# HIVE_BOARD_MISC.net
KiCad netlist of a schematic drawn in Altium Designer
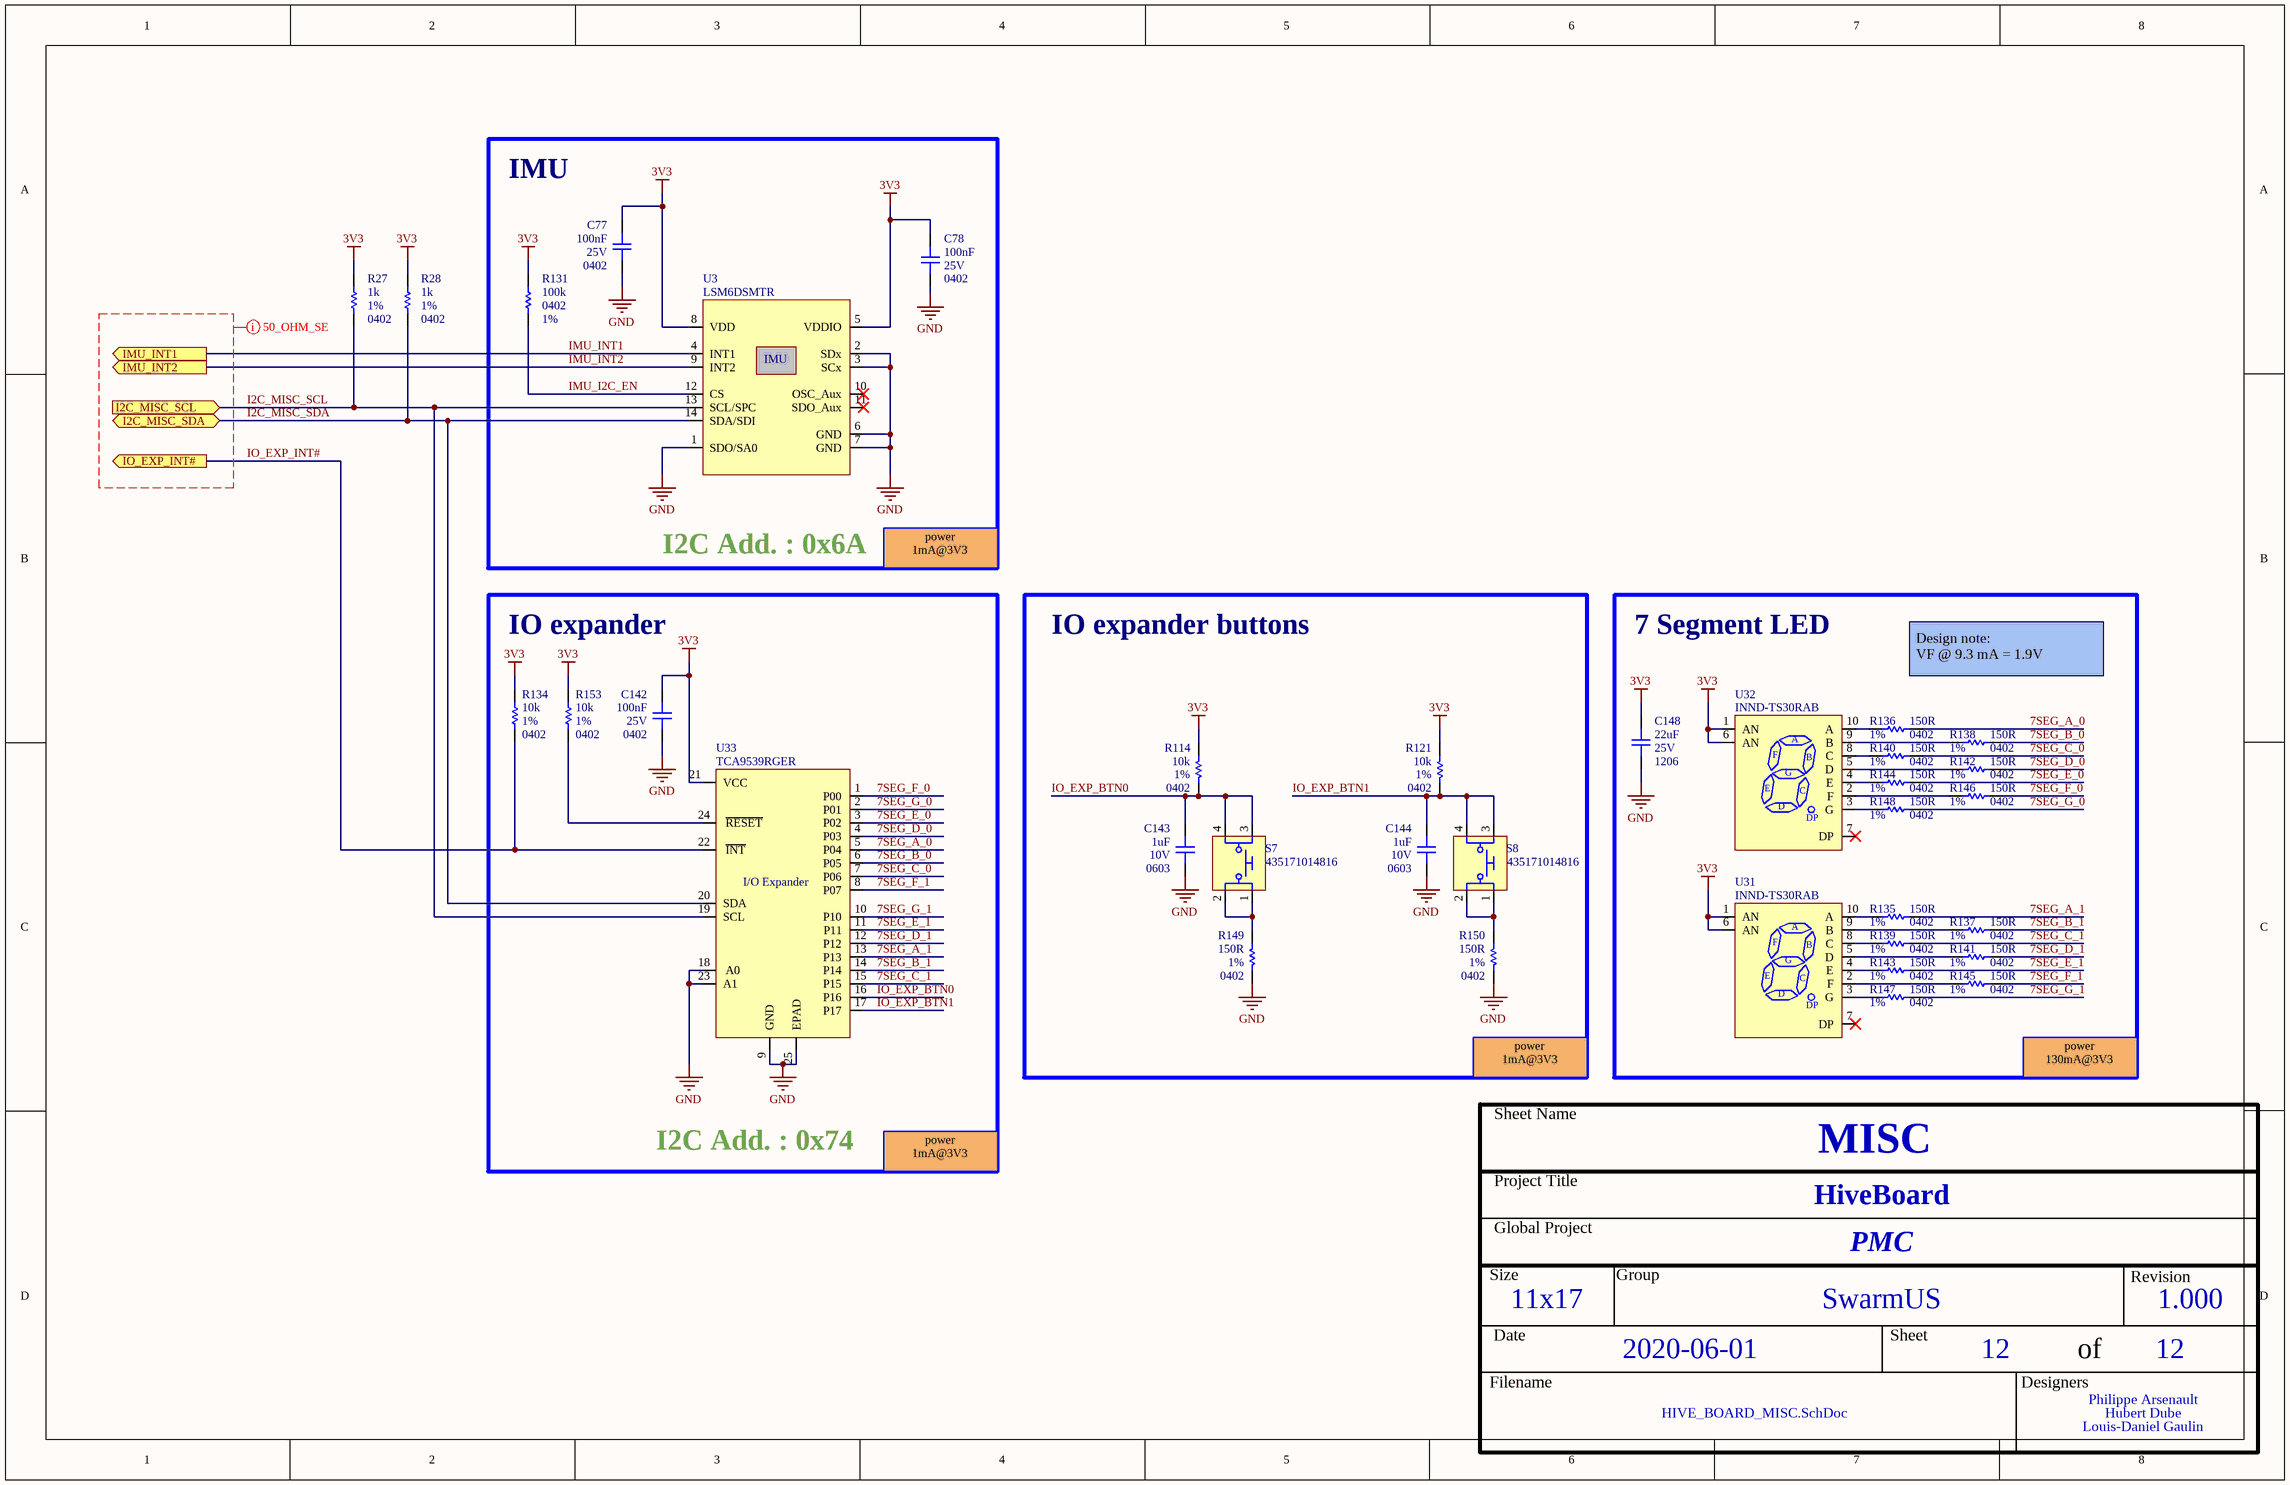
[diagram p0: HIVE_BOARD_MISC.SchDoc]

(export (version "E")
  (design (tool "Eeschema 10.0.6"))
  (components
    (comp (ref "C77")
      (value "100nF")
      (footprint "CAP_CER_0402")
      (description "CAP - CER 0.1µF 10% 25V X7R - 0402")
      (fields
        (field (name "TOLERANCE") "10%")
        (field (name "PACKAGE") "0402")
        (field (name "VOLTAGE RATING") "25V")
        (field (name "Comment") "CGA2B3X7R1E104K050BB")
        (field (name "CREATEDBY/DATE") "Nicolas Roy 2018-11-07")
        (field (name "VERIFIEDBY") "Nicolas V. (2019-01-22)")
      )
      (libsource (lib "GRAMS_MASTER_LIB") (part "CAP_CER_CGA2B3X7R1E104K050BB"))
    )
    (comp (ref "C78")
      (value "100nF")
      (footprint "CAP_CER_0402")
      (description "CAP - CER 0.1µF 10% 25V X7R - 0402")
      (fields
        (field (name "TOLERANCE") "10%")
        (field (name "PACKAGE") "0402")
        (field (name "VOLTAGE RATING") "25V")
        (field (name "Comment") "CGA2B3X7R1E104K050BB")
        (field (name "CREATEDBY/DATE") "Nicolas Roy 2018-11-07")
        (field (name "VERIFIEDBY") "Nicolas V. (2019-01-22)")
      )
      (libsource (lib "GRAMS_MASTER_LIB") (part "CAP_CER_CGA2B3X7R1E104K050BB"))
    )
    (comp (ref "C142")
      (value "100nF")
      (footprint "CAP_CER_0402")
      (description "CAP - CER 0.1µF 10% 25V X7R - 0402")
      (fields
        (field (name "TOLERANCE") "10%")
        (field (name "PACKAGE") "0402")
        (field (name "VOLTAGE RATING") "25V")
        (field (name "Comment") "CGA2B3X7R1E104K050BB")
        (field (name "CREATEDBY/DATE") "Nicolas Roy 2018-11-07")
        (field (name "VERIFIEDBY") "Nicolas V. (2019-01-22)")
      )
      (libsource (lib "GRAMS_MASTER_LIB") (part "CAP_CER_CGA2B3X7R1E104K050BB"))
    )
    (comp (ref "C143")
      (value "1uF")
      (footprint "CAP_CER_0603")
      (description "CAP - CER 1uF 10V 10% X5R - 0603")
      (fields
        (field (name "TOLERANCE") "10%")
        (field (name "PACKAGE") "0603")
        (field (name "VOLTAGE RATING") "10V")
        (field (name "Comment") "C0603C105K8PACTU")
        (field (name "CREATEDBY/DATE") "Hubert Dube - 21/07/20")
        (field (name "VERIFIEDBY") "Louis-Daniel Gaulin - 21/07/20")
      )
      (libsource (lib "SWARMUS_LIB") (part "CAP_CER_C0603C105K8PACTU"))
    )
    (comp (ref "C144")
      (value "1uF")
      (footprint "CAP_CER_0603")
      (description "CAP - CER 1uF 10V 10% X5R - 0603")
      (fields
        (field (name "TOLERANCE") "10%")
        (field (name "PACKAGE") "0603")
        (field (name "VOLTAGE RATING") "10V")
        (field (name "Comment") "C0603C105K8PACTU")
        (field (name "CREATEDBY/DATE") "Hubert Dube - 21/07/20")
        (field (name "VERIFIEDBY") "Louis-Daniel Gaulin - 21/07/20")
      )
      (libsource (lib "SWARMUS_LIB") (part "CAP_CER_C0603C105K8PACTU"))
    )
    (comp (ref "C148")
      (value "22uF")
      (footprint "CAP_CER_1206")
      (description "CAP - CER 22uF 10% 25V X5R - 1206")
      (fields
        (field (name "TOLERANCE") "10%")
        (field (name "PACKAGE") "1206")
        (field (name "VOLTAGE RATING") "25V")
        (field (name "Comment") "CL31A226KAHNNNE")
        (field (name "CREATEDBY/DATE") "Philippe Arsenault/21 Janvier 2020")
        (field (name "VERIFIEDBY") "C.Paulin - 28/01/2020")
      )
      (libsource (lib "GRAMS_MASTER_LIB") (part "CAP_CER_CL31A226KAHNNNE"))
    )
    (comp (ref "R27")
      (value "1k")
      (footprint "RES_0402")
      (description "RES - 1K OHM 1% 1/16W - 0402")
      (fields
        (field (name "TOLERANCE") "1%")
        (field (name "PACKAGE") "0402")
        (field (name "Comment") "RC0402FR-071KL")
        (field (name "CREATEDBY/DATE") "Jonathan Bouchard 2018-07-05")
        (field (name "VERIFIEDBY") "Arnaud Samson 16-07-18")
      )
      (libsource (lib "GRAMS_MASTER_LIB") (part "RES_RC0402FR-071KL"))
    )
    (comp (ref "R28")
      (value "1k")
      (footprint "RES_0402")
      (description "RES - 1K OHM 1% 1/16W - 0402")
      (fields
        (field (name "TOLERANCE") "1%")
        (field (name "PACKAGE") "0402")
        (field (name "Comment") "RC0402FR-071KL")
        (field (name "CREATEDBY/DATE") "Jonathan Bouchard 2018-07-05")
        (field (name "VERIFIEDBY") "Arnaud Samson 16-07-18")
      )
      (libsource (lib "GRAMS_MASTER_LIB") (part "RES_RC0402FR-071KL"))
    )
    (comp (ref "R114")
      (value "10k")
      (footprint "RES_0402")
      (description "RES - 10K OHMS 1% 1/16W - 0402")
      (fields
        (field (name "TOLERANCE") "1%")
        (field (name "PACKAGE") "0402")
        (field (name "Comment") "RC0402FR-0710KL")
        (field (name "CREATEDBY/DATE") "Nicolas V. (2018-11-20)")
        (field (name "VERIFIEDBY") "Nicolas V. (2018-11-20)")
      )
      (libsource (lib "GRAMS_MASTER_LIB") (part "RES_RC0402FR-0710KL"))
    )
    (comp (ref "R121")
      (value "10k")
      (footprint "RES_0402")
      (description "RES - 10K OHMS 1% 1/16W - 0402")
      (fields
        (field (name "TOLERANCE") "1%")
        (field (name "PACKAGE") "0402")
        (field (name "Comment") "RC0402FR-0710KL")
        (field (name "CREATEDBY/DATE") "Nicolas V. (2018-11-20)")
        (field (name "VERIFIEDBY") "Nicolas V. (2018-11-20)")
      )
      (libsource (lib "GRAMS_MASTER_LIB") (part "RES_RC0402FR-0710KL"))
    )
    (comp (ref "R131")
      (value "100k")
      (footprint "RES_0402")
      (description "RES - 100K 1% 1/16W - 0402")
      (fields
        (field (name "TOLERANCE") "1%")
        (field (name "PACKAGE") "0402")
        (field (name "Comment") "RC0402FR-07100KL")
        (field (name "CREATEDBY/DATE") "Keven Deslandes 2018-10-19")
        (field (name "VERIFIEDBY") "Caroline Paulin - 18/12/2018")
      )
      (libsource (lib "GRAMS_MASTER_LIB") (part "RES_RC0402FR-07100KL"))
    )
    (comp (ref "R134")
      (value "10k")
      (footprint "RES_0402")
      (description "RES - 10K OHMS 1% 1/16W - 0402")
      (fields
        (field (name "TOLERANCE") "1%")
        (field (name "PACKAGE") "0402")
        (field (name "Comment") "RC0402FR-0710KL")
        (field (name "CREATEDBY/DATE") "Nicolas V. (2018-11-20)")
        (field (name "VERIFIEDBY") "Nicolas V. (2018-11-20)")
      )
      (libsource (lib "GRAMS_MASTER_LIB") (part "RES_RC0402FR-0710KL"))
    )
    (comp (ref "R135")
      (value "150R")
      (footprint "RES_0402")
      (description "RES - 150R 1% 1/16W - 0402")
      (fields
        (field (name "TOLERANCE") "1%")
        (field (name "PACKAGE") "0402")
        (field (name "Comment") "RC0402FR-07150RL")
        (field (name "CREATEDBY/DATE") "Jonathan Bouchard 2019-03-25")
        (field (name "VERIFIEDBY") "Nicolas V. (2019-05-02)")
      )
      (libsource (lib "GRAMS_MASTER_LIB") (part "RES_RC0402FR-07150RL"))
    )
    (comp (ref "R136")
      (value "150R")
      (footprint "RES_0402")
      (description "RES - 150R 1% 1/16W - 0402")
      (fields
        (field (name "TOLERANCE") "1%")
        (field (name "PACKAGE") "0402")
        (field (name "Comment") "RC0402FR-07150RL")
        (field (name "CREATEDBY/DATE") "Jonathan Bouchard 2019-03-25")
        (field (name "VERIFIEDBY") "Nicolas V. (2019-05-02)")
      )
      (libsource (lib "GRAMS_MASTER_LIB") (part "RES_RC0402FR-07150RL"))
    )
    (comp (ref "R137")
      (value "150R")
      (footprint "RES_0402")
      (description "RES - 150R 1% 1/16W - 0402")
      (fields
        (field (name "TOLERANCE") "1%")
        (field (name "PACKAGE") "0402")
        (field (name "Comment") "RC0402FR-07150RL")
        (field (name "CREATEDBY/DATE") "Jonathan Bouchard 2019-03-25")
        (field (name "VERIFIEDBY") "Nicolas V. (2019-05-02)")
      )
      (libsource (lib "GRAMS_MASTER_LIB") (part "RES_RC0402FR-07150RL"))
    )
    (comp (ref "R138")
      (value "150R")
      (footprint "RES_0402")
      (description "RES - 150R 1% 1/16W - 0402")
      (fields
        (field (name "TOLERANCE") "1%")
        (field (name "PACKAGE") "0402")
        (field (name "Comment") "RC0402FR-07150RL")
        (field (name "CREATEDBY/DATE") "Jonathan Bouchard 2019-03-25")
        (field (name "VERIFIEDBY") "Nicolas V. (2019-05-02)")
      )
      (libsource (lib "GRAMS_MASTER_LIB") (part "RES_RC0402FR-07150RL"))
    )
    (comp (ref "R139")
      (value "150R")
      (footprint "RES_0402")
      (description "RES - 150R 1% 1/16W - 0402")
      (fields
        (field (name "TOLERANCE") "1%")
        (field (name "PACKAGE") "0402")
        (field (name "Comment") "RC0402FR-07150RL")
        (field (name "CREATEDBY/DATE") "Jonathan Bouchard 2019-03-25")
        (field (name "VERIFIEDBY") "Nicolas V. (2019-05-02)")
      )
      (libsource (lib "GRAMS_MASTER_LIB") (part "RES_RC0402FR-07150RL"))
    )
    (comp (ref "R140")
      (value "150R")
      (footprint "RES_0402")
      (description "RES - 150R 1% 1/16W - 0402")
      (fields
        (field (name "TOLERANCE") "1%")
        (field (name "PACKAGE") "0402")
        (field (name "Comment") "RC0402FR-07150RL")
        (field (name "CREATEDBY/DATE") "Jonathan Bouchard 2019-03-25")
        (field (name "VERIFIEDBY") "Nicolas V. (2019-05-02)")
      )
      (libsource (lib "GRAMS_MASTER_LIB") (part "RES_RC0402FR-07150RL"))
    )
    (comp (ref "R141")
      (value "150R")
      (footprint "RES_0402")
      (description "RES - 150R 1% 1/16W - 0402")
      (fields
        (field (name "TOLERANCE") "1%")
        (field (name "PACKAGE") "0402")
        (field (name "Comment") "RC0402FR-07150RL")
        (field (name "CREATEDBY/DATE") "Jonathan Bouchard 2019-03-25")
        (field (name "VERIFIEDBY") "Nicolas V. (2019-05-02)")
      )
      (libsource (lib "GRAMS_MASTER_LIB") (part "RES_RC0402FR-07150RL"))
    )
    (comp (ref "R142")
      (value "150R")
      (footprint "RES_0402")
      (description "RES - 150R 1% 1/16W - 0402")
      (fields
        (field (name "TOLERANCE") "1%")
        (field (name "PACKAGE") "0402")
        (field (name "Comment") "RC0402FR-07150RL")
        (field (name "CREATEDBY/DATE") "Jonathan Bouchard 2019-03-25")
        (field (name "VERIFIEDBY") "Nicolas V. (2019-05-02)")
      )
      (libsource (lib "GRAMS_MASTER_LIB") (part "RES_RC0402FR-07150RL"))
    )
    (comp (ref "R143")
      (value "150R")
      (footprint "RES_0402")
      (description "RES - 150R 1% 1/16W - 0402")
      (fields
        (field (name "TOLERANCE") "1%")
        (field (name "PACKAGE") "0402")
        (field (name "Comment") "RC0402FR-07150RL")
        (field (name "CREATEDBY/DATE") "Jonathan Bouchard 2019-03-25")
        (field (name "VERIFIEDBY") "Nicolas V. (2019-05-02)")
      )
      (libsource (lib "GRAMS_MASTER_LIB") (part "RES_RC0402FR-07150RL"))
    )
    (comp (ref "R144")
      (value "150R")
      (footprint "RES_0402")
      (description "RES - 150R 1% 1/16W - 0402")
      (fields
        (field (name "TOLERANCE") "1%")
        (field (name "PACKAGE") "0402")
        (field (name "Comment") "RC0402FR-07150RL")
        (field (name "CREATEDBY/DATE") "Jonathan Bouchard 2019-03-25")
        (field (name "VERIFIEDBY") "Nicolas V. (2019-05-02)")
      )
      (libsource (lib "GRAMS_MASTER_LIB") (part "RES_RC0402FR-07150RL"))
    )
    (comp (ref "R145")
      (value "150R")
      (footprint "RES_0402")
      (description "RES - 150R 1% 1/16W - 0402")
      (fields
        (field (name "TOLERANCE") "1%")
        (field (name "PACKAGE") "0402")
        (field (name "Comment") "RC0402FR-07150RL")
        (field (name "CREATEDBY/DATE") "Jonathan Bouchard 2019-03-25")
        (field (name "VERIFIEDBY") "Nicolas V. (2019-05-02)")
      )
      (libsource (lib "GRAMS_MASTER_LIB") (part "RES_RC0402FR-07150RL"))
    )
    (comp (ref "R146")
      (value "150R")
      (footprint "RES_0402")
      (description "RES - 150R 1% 1/16W - 0402")
      (fields
        (field (name "TOLERANCE") "1%")
        (field (name "PACKAGE") "0402")
        (field (name "Comment") "RC0402FR-07150RL")
        (field (name "CREATEDBY/DATE") "Jonathan Bouchard 2019-03-25")
        (field (name "VERIFIEDBY") "Nicolas V. (2019-05-02)")
      )
      (libsource (lib "GRAMS_MASTER_LIB") (part "RES_RC0402FR-07150RL"))
    )
    (comp (ref "R147")
      (value "150R")
      (footprint "RES_0402")
      (description "RES - 150R 1% 1/16W - 0402")
      (fields
        (field (name "TOLERANCE") "1%")
        (field (name "PACKAGE") "0402")
        (field (name "Comment") "RC0402FR-07150RL")
        (field (name "CREATEDBY/DATE") "Jonathan Bouchard 2019-03-25")
        (field (name "VERIFIEDBY") "Nicolas V. (2019-05-02)")
      )
      (libsource (lib "GRAMS_MASTER_LIB") (part "RES_RC0402FR-07150RL"))
    )
    (comp (ref "R148")
      (value "150R")
      (footprint "RES_0402")
      (description "RES - 150R 1% 1/16W - 0402")
      (fields
        (field (name "TOLERANCE") "1%")
        (field (name "PACKAGE") "0402")
        (field (name "Comment") "RC0402FR-07150RL")
        (field (name "CREATEDBY/DATE") "Jonathan Bouchard 2019-03-25")
        (field (name "VERIFIEDBY") "Nicolas V. (2019-05-02)")
      )
      (libsource (lib "GRAMS_MASTER_LIB") (part "RES_RC0402FR-07150RL"))
    )
    (comp (ref "R149")
      (value "150R")
      (footprint "RES_0402")
      (description "RES - 150R 1% 1/16W - 0402")
      (fields
        (field (name "TOLERANCE") "1%")
        (field (name "PACKAGE") "0402")
        (field (name "Comment") "RC0402FR-07150RL")
        (field (name "CREATEDBY/DATE") "Jonathan Bouchard 2019-03-25")
        (field (name "VERIFIEDBY") "Nicolas V. (2019-05-02)")
      )
      (libsource (lib "GRAMS_MASTER_LIB") (part "RES_RC0402FR-07150RL"))
    )
    (comp (ref "R150")
      (value "150R")
      (footprint "RES_0402")
      (description "RES - 150R 1% 1/16W - 0402")
      (fields
        (field (name "TOLERANCE") "1%")
        (field (name "PACKAGE") "0402")
        (field (name "Comment") "RC0402FR-07150RL")
        (field (name "CREATEDBY/DATE") "Jonathan Bouchard 2019-03-25")
        (field (name "VERIFIEDBY") "Nicolas V. (2019-05-02)")
      )
      (libsource (lib "GRAMS_MASTER_LIB") (part "RES_RC0402FR-07150RL"))
    )
    (comp (ref "R153")
      (value "10k")
      (footprint "RES_0402")
      (description "RES - 10K OHMS 1% 1/16W - 0402")
      (fields
        (field (name "TOLERANCE") "1%")
        (field (name "PACKAGE") "0402")
        (field (name "Comment") "RC0402FR-0710KL")
        (field (name "CREATEDBY/DATE") "Nicolas V. (2018-11-20)")
        (field (name "VERIFIEDBY") "Nicolas V. (2018-11-20)")
      )
      (libsource (lib "GRAMS_MASTER_LIB") (part "RES_RC0402FR-0710KL"))
    )
    (comp (ref "S7")
      (value "435171014816")
      (footprint "SWI_TACT_435171014816")
      (description "SWI - SWITCH TACTILE SPST-NO 0.05A 12V -SMD")
      (fields
        (field (name "CREATEDBY/DATE") "Hubert Dube - 22/07/20")
        (field (name "VERIFIEDBY") "Louis-Daniel Gaulin / 12-11-2020")
      )
      (libsource (lib "SWARMUS_LIB") (part "SWI_TACT_435171014816"))
    )
    (comp (ref "S8")
      (value "435171014816")
      (footprint "SWI_TACT_435171014816")
      (description "SWI - SWITCH TACTILE SPST-NO 0.05A 12V -SMD")
      (fields
        (field (name "CREATEDBY/DATE") "Hubert Dube - 22/07/20")
        (field (name "VERIFIEDBY") "Louis-Daniel Gaulin / 12-11-2020")
      )
      (libsource (lib "SWARMUS_LIB") (part "SWI_TACT_435171014816"))
    )
    (comp (ref "U3")
      (value "LSM6DSMTR")
      (footprint "SEN_IMU_LSM6DSMTR")
      (description "SEN_IMU -  ACCEL/GYRO 6 Axis I2C/SPI - 14-VFLGA")
      (fields
        (field (name "CREATEDBY/DATE") "Louis-Daniel Gaulin / 06-10-2020")
        (field (name "VERIFIEDBY") "Philippe Arsenault/2020-11-06")
      )
      (libsource (lib "SWARMUS_LIB") (part "SEN_IMU_LSM6DSMTR"))
    )
    (comp (ref "U31")
      (value "INND-TS30RAB")
      (footprint "LED_7SEG_INND-TS30RAB")
      (description "LED_7SEG  - LED Character and Numeric Red 7-Segment 1 Character Common Anode 2V - 10-TH")
      (fields
        (field (name "CREATEDBY/DATE") "Louis-Daniel Gaulin / 10-05-2021")
        (field (name "VERIFIEDBY") "Philippe Arsenault/10-05-2021")
      )
      (libsource (lib "SWARMUS_LIB") (part "LED_7SEG_INND-TS30RAB"))
    )
    (comp (ref "U32")
      (value "INND-TS30RAB")
      (footprint "LED_7SEG_INND-TS30RAB")
      (description "LED_7SEG  - LED Character and Numeric Red 7-Segment 1 Character Common Anode 2V - 10-TH")
      (fields
        (field (name "CREATEDBY/DATE") "Louis-Daniel Gaulin / 10-05-2021")
        (field (name "VERIFIEDBY") "Philippe Arsenault/10-05-2021")
      )
      (libsource (lib "SWARMUS_LIB") (part "LED_7SEG_INND-TS30RAB"))
    )
    (comp (ref "U33")
      (value "TCA9539RGER")
      (footprint "LOG_IOEXP_TCA9539RGER")
      (description "LOG - 16-Bit I2C/SMBus, I/O Expander - 24-VQFN-EP")
      (fields
        (field (name "CREATEDBY/DATE") "Louis-Daniel Gaulin / 10-05-2021")
        (field (name "VERIFIEDBY") "Philippe Arsenault/2021-05-10")
      )
      (libsource (lib "SWARMUS_LIB") (part "LOG_IOEXP_TCA9539RGER"))
    )
  )
  (nets
    (net (code "1") (name "/7SEG_A_0") (class "Default")
      (node (ref "R136") (pin "1") (pinfunction "1_1") (pintype "passive"))
      (node (ref "U33") (pin "5") (pinfunction "P04_5") (pintype "passive"))
    )
    (net (code "2") (name "/7SEG_A_1") (class "Default")
      (node (ref "R135") (pin "1") (pinfunction "1_1") (pintype "passive"))
      (node (ref "U33") (pin "13") (pinfunction "P13_13") (pintype "passive"))
    )
    (net (code "3") (name "/7SEG_B_0") (class "Default")
      (node (ref "R138") (pin "1") (pinfunction "1_1") (pintype "passive"))
      (node (ref "U33") (pin "6") (pinfunction "P05_6") (pintype "passive"))
    )
    (net (code "4") (name "/7SEG_B_1") (class "Default")
      (node (ref "R137") (pin "1") (pinfunction "1_1") (pintype "passive"))
      (node (ref "U33") (pin "14") (pinfunction "P14_14") (pintype "passive"))
    )
    (net (code "5") (name "/7SEG_C_0") (class "Default")
      (node (ref "R140") (pin "1") (pinfunction "1_1") (pintype "passive"))
      (node (ref "U33") (pin "7") (pinfunction "P06_7") (pintype "passive"))
    )
    (net (code "6") (name "/7SEG_C_1") (class "Default")
      (node (ref "R139") (pin "1") (pinfunction "1_1") (pintype "passive"))
      (node (ref "U33") (pin "15") (pinfunction "P15_15") (pintype "passive"))
    )
    (net (code "7") (name "/7SEG_D_0") (class "Default")
      (node (ref "R142") (pin "1") (pinfunction "1_1") (pintype "passive"))
      (node (ref "U33") (pin "4") (pinfunction "P03_4") (pintype "passive"))
    )
    (net (code "8") (name "/7SEG_D_1") (class "Default")
      (node (ref "R141") (pin "1") (pinfunction "1_1") (pintype "passive"))
      (node (ref "U33") (pin "12") (pinfunction "P12_12") (pintype "passive"))
    )
    (net (code "9") (name "/7SEG_E_0") (class "Default")
      (node (ref "R144") (pin "1") (pinfunction "1_1") (pintype "passive"))
      (node (ref "U33") (pin "3") (pinfunction "P02_3") (pintype "passive"))
    )
    (net (code "10") (name "/7SEG_E_1") (class "Default")
      (node (ref "R143") (pin "1") (pinfunction "1_1") (pintype "passive"))
      (node (ref "U33") (pin "11") (pinfunction "P11_11") (pintype "passive"))
    )
    (net (code "11") (name "/7SEG_F_0") (class "Default")
      (node (ref "R146") (pin "1") (pinfunction "1_1") (pintype "passive"))
      (node (ref "U33") (pin "1") (pinfunction "P00_1") (pintype "passive"))
    )
    (net (code "12") (name "/7SEG_F_1") (class "Default")
      (node (ref "R145") (pin "1") (pinfunction "1_1") (pintype "passive"))
      (node (ref "U33") (pin "8") (pinfunction "P07_8") (pintype "passive"))
    )
    (net (code "13") (name "/7SEG_G_0") (class "Default")
      (node (ref "R148") (pin "1") (pinfunction "1_1") (pintype "passive"))
      (node (ref "U33") (pin "2") (pinfunction "P01_2") (pintype "passive"))
    )
    (net (code "14") (name "/7SEG_G_1") (class "Default")
      (node (ref "R147") (pin "1") (pinfunction "1_1") (pintype "passive"))
      (node (ref "U33") (pin "10") (pinfunction "P10_10") (pintype "passive"))
    )
    (net (code "15") (name "/I2C_MISC_SCL") (class "Default")
      (node (ref "R27") (pin "2") (pinfunction "2_2") (pintype "passive"))
      (node (ref "U3") (pin "13") (pinfunction "SCL/SPC_13") (pintype "passive"))
      (node (ref "U33") (pin "19") (pinfunction "SCL_19") (pintype "passive"))
    )
    (net (code "16") (name "/I2C_MISC_SDA") (class "Default")
      (node (ref "R28") (pin "2") (pinfunction "2_2") (pintype "passive"))
      (node (ref "U3") (pin "14") (pinfunction "SDA/SDI_14") (pintype "passive"))
      (node (ref "U33") (pin "20") (pinfunction "SDA_20") (pintype "passive"))
    )
    (net (code "17") (name "/IMU_I2C_EN") (class "Default")
      (node (ref "R131") (pin "2") (pinfunction "2_2") (pintype "passive"))
      (node (ref "U3") (pin "12") (pinfunction "CS_12") (pintype "passive"))
    )
    (net (code "18") (name "/IMU_INT1") (class "Default")
      (node (ref "U3") (pin "4") (pinfunction "INT1_4") (pintype "passive"))
    )
    (net (code "19") (name "/IMU_INT2") (class "Default")
      (node (ref "U3") (pin "9") (pinfunction "INT2_9") (pintype "passive"))
    )
    (net (code "20") (name "/IO_EXP_BTN0") (class "Default")
      (node (ref "C143") (pin "1") (pinfunction "1_1") (pintype "passive"))
      (node (ref "R114") (pin "1") (pinfunction "1_1") (pintype "passive"))
      (node (ref "S7") (pin "3") (pinfunction "3_3") (pintype "passive"))
      (node (ref "S7") (pin "4") (pinfunction "4_4") (pintype "passive"))
      (node (ref "U33") (pin "16") (pinfunction "P16_16") (pintype "passive"))
    )
    (net (code "21") (name "/IO_EXP_BTN1") (class "Default")
      (node (ref "C144") (pin "1") (pinfunction "1_1") (pintype "passive"))
      (node (ref "R121") (pin "1") (pinfunction "1_1") (pintype "passive"))
      (node (ref "S8") (pin "3") (pinfunction "3_3") (pintype "passive"))
      (node (ref "S8") (pin "4") (pinfunction "4_4") (pintype "passive"))
      (node (ref "U33") (pin "17") (pinfunction "P17_17") (pintype "passive"))
    )
    (net (code "22") (name "/IO_EXP_INT#") (class "Default")
      (node (ref "R134") (pin "1") (pinfunction "1_1") (pintype "passive"))
      (node (ref "U33") (pin "22") (pinfunction "INT_22") (pintype "passive"))
    )
    (net (code "23") (name "3V3") (class "Default")
      (node (ref "C142") (pin "1") (pinfunction "1_1") (pintype "passive"))
      (node (ref "C148") (pin "2") (pinfunction "2_2") (pintype "passive"))
      (node (ref "C77") (pin "1") (pinfunction "1_1") (pintype "passive"))
      (node (ref "C78") (pin "1") (pinfunction "1_1") (pintype "passive"))
      (node (ref "R114") (pin "2") (pinfunction "2_2") (pintype "passive"))
      (node (ref "R121") (pin "2") (pinfunction "2_2") (pintype "passive"))
      (node (ref "R131") (pin "1") (pinfunction "1_1") (pintype "passive"))
      (node (ref "R134") (pin "2") (pinfunction "2_2") (pintype "passive"))
      (node (ref "R153") (pin "2") (pinfunction "2_2") (pintype "passive"))
      (node (ref "R27") (pin "1") (pinfunction "1_1") (pintype "passive"))
      (node (ref "R28") (pin "1") (pinfunction "1_1") (pintype "passive"))
      (node (ref "U3") (pin "5") (pinfunction "VDDIO_5") (pintype "passive"))
      (node (ref "U3") (pin "8") (pinfunction "VDD_8") (pintype "passive"))
      (node (ref "U31") (pin "1") (pinfunction "AN_1") (pintype "passive"))
      (node (ref "U31") (pin "6") (pinfunction "AN_6") (pintype "passive"))
      (node (ref "U32") (pin "1") (pinfunction "AN_1") (pintype "passive"))
      (node (ref "U32") (pin "6") (pinfunction "AN_6") (pintype "passive"))
      (node (ref "U33") (pin "21") (pinfunction "VCC_21") (pintype "passive"))
    )
    (net (code "24") (name "GND") (class "Default")
      (node (ref "C142") (pin "2") (pinfunction "2_2") (pintype "passive"))
      (node (ref "C143") (pin "2") (pinfunction "2_2") (pintype "passive"))
      (node (ref "C144") (pin "2") (pinfunction "2_2") (pintype "passive"))
      (node (ref "C148") (pin "1") (pinfunction "1_1") (pintype "passive"))
      (node (ref "C77") (pin "2") (pinfunction "2_2") (pintype "passive"))
      (node (ref "C78") (pin "2") (pinfunction "2_2") (pintype "passive"))
      (node (ref "R149") (pin "1") (pinfunction "1_1") (pintype "passive"))
      (node (ref "R150") (pin "1") (pinfunction "1_1") (pintype "passive"))
      (node (ref "U3") (pin "1") (pinfunction "SDO/SA0_1") (pintype "passive"))
      (node (ref "U3") (pin "2") (pinfunction "SDx_2") (pintype "passive"))
      (node (ref "U3") (pin "3") (pinfunction "SCx_3") (pintype "passive"))
      (node (ref "U3") (pin "6") (pinfunction "GND_6") (pintype "passive"))
      (node (ref "U3") (pin "7") (pinfunction "GND_7") (pintype "passive"))
      (node (ref "U33") (pin "18") (pinfunction "A0_18") (pintype "passive"))
      (node (ref "U33") (pin "23") (pinfunction "A1_23") (pintype "passive"))
      (node (ref "U33") (pin "25") (pinfunction "EPAD_25") (pintype "passive"))
      (node (ref "U33") (pin "9") (pinfunction "GND_9") (pintype "passive"))
    )
    (net (code "25") (name "Net-(R149-Pad2)") (class "Default")
      (node (ref "R149") (pin "2") (pinfunction "2_2") (pintype "passive"))
      (node (ref "S7") (pin "1") (pinfunction "1_1") (pintype "passive"))
      (node (ref "S7") (pin "2") (pinfunction "2_2") (pintype "passive"))
    )
    (net (code "26") (name "Net-(R150-Pad2)") (class "Default")
      (node (ref "R150") (pin "2") (pinfunction "2_2") (pintype "passive"))
      (node (ref "S8") (pin "1") (pinfunction "1_1") (pintype "passive"))
      (node (ref "S8") (pin "2") (pinfunction "2_2") (pintype "passive"))
    )
    (net (code "27") (name "Net-(U31-A)") (class "Default")
      (node (ref "R135") (pin "2") (pinfunction "2_2") (pintype "passive"))
      (node (ref "U31") (pin "10") (pinfunction "A_10") (pintype "passive"))
    )
    (net (code "28") (name "Net-(U31-B)") (class "Default")
      (node (ref "R137") (pin "2") (pinfunction "2_2") (pintype "passive"))
      (node (ref "U31") (pin "9") (pinfunction "B_9") (pintype "passive"))
    )
    (net (code "29") (name "Net-(U31-C)") (class "Default")
      (node (ref "R139") (pin "2") (pinfunction "2_2") (pintype "passive"))
      (node (ref "U31") (pin "8") (pinfunction "C_8") (pintype "passive"))
    )
    (net (code "30") (name "Net-(U31-D)") (class "Default")
      (node (ref "R141") (pin "2") (pinfunction "2_2") (pintype "passive"))
      (node (ref "U31") (pin "5") (pinfunction "D_5") (pintype "passive"))
    )
    (net (code "31") (name "Net-(U31-E)") (class "Default")
      (node (ref "R143") (pin "2") (pinfunction "2_2") (pintype "passive"))
      (node (ref "U31") (pin "4") (pinfunction "E_4") (pintype "passive"))
    )
    (net (code "32") (name "Net-(U31-F)") (class "Default")
      (node (ref "R145") (pin "2") (pinfunction "2_2") (pintype "passive"))
      (node (ref "U31") (pin "2") (pinfunction "F_2") (pintype "passive"))
    )
    (net (code "33") (name "Net-(U31-G)") (class "Default")
      (node (ref "R147") (pin "2") (pinfunction "2_2") (pintype "passive"))
      (node (ref "U31") (pin "3") (pinfunction "G_3") (pintype "passive"))
    )
    (net (code "34") (name "Net-(U32-A)") (class "Default")
      (node (ref "R136") (pin "2") (pinfunction "2_2") (pintype "passive"))
      (node (ref "U32") (pin "10") (pinfunction "A_10") (pintype "passive"))
    )
    (net (code "35") (name "Net-(U32-B)") (class "Default")
      (node (ref "R138") (pin "2") (pinfunction "2_2") (pintype "passive"))
      (node (ref "U32") (pin "9") (pinfunction "B_9") (pintype "passive"))
    )
    (net (code "36") (name "Net-(U32-C)") (class "Default")
      (node (ref "R140") (pin "2") (pinfunction "2_2") (pintype "passive"))
      (node (ref "U32") (pin "8") (pinfunction "C_8") (pintype "passive"))
    )
    (net (code "37") (name "Net-(U32-D)") (class "Default")
      (node (ref "R142") (pin "2") (pinfunction "2_2") (pintype "passive"))
      (node (ref "U32") (pin "5") (pinfunction "D_5") (pintype "passive"))
    )
    (net (code "38") (name "Net-(U32-E)") (class "Default")
      (node (ref "R144") (pin "2") (pinfunction "2_2") (pintype "passive"))
      (node (ref "U32") (pin "4") (pinfunction "E_4") (pintype "passive"))
    )
    (net (code "39") (name "Net-(U32-F)") (class "Default")
      (node (ref "R146") (pin "2") (pinfunction "2_2") (pintype "passive"))
      (node (ref "U32") (pin "2") (pinfunction "F_2") (pintype "passive"))
    )
    (net (code "40") (name "Net-(U32-G)") (class "Default")
      (node (ref "R148") (pin "2") (pinfunction "2_2") (pintype "passive"))
      (node (ref "U32") (pin "3") (pinfunction "G_3") (pintype "passive"))
    )
    (net (code "41") (name "Net-(U33-RESET)") (class "Default")
      (node (ref "R153") (pin "1") (pinfunction "1_1") (pintype "passive"))
      (node (ref "U33") (pin "24") (pinfunction "RESET_24") (pintype "passive"))
    )
    (net (code "42") (name "unconnected-(U3-OSC_Aux-Pad10)") (class "Default")
      (node (ref "U3") (pin "10") (pinfunction "OSC_Aux_10") (pintype "passive+no_connect"))
    )
    (net (code "43") (name "unconnected-(U3-SDO_Aux-Pad11)") (class "Default")
      (node (ref "U3") (pin "11") (pinfunction "SDO_Aux_11") (pintype "passive+no_connect"))
    )
    (net (code "44") (name "unconnected-(U31-DP-Pad7)") (class "Default")
      (node (ref "U31") (pin "7") (pinfunction "DP_7") (pintype "passive+no_connect"))
    )
    (net (code "45") (name "unconnected-(U32-DP-Pad7)") (class "Default")
      (node (ref "U32") (pin "7") (pinfunction "DP_7") (pintype "passive+no_connect"))
    )
  )
)
